# MOSFET.net
KiCad netlist of a schematic drawn in Altium Designer
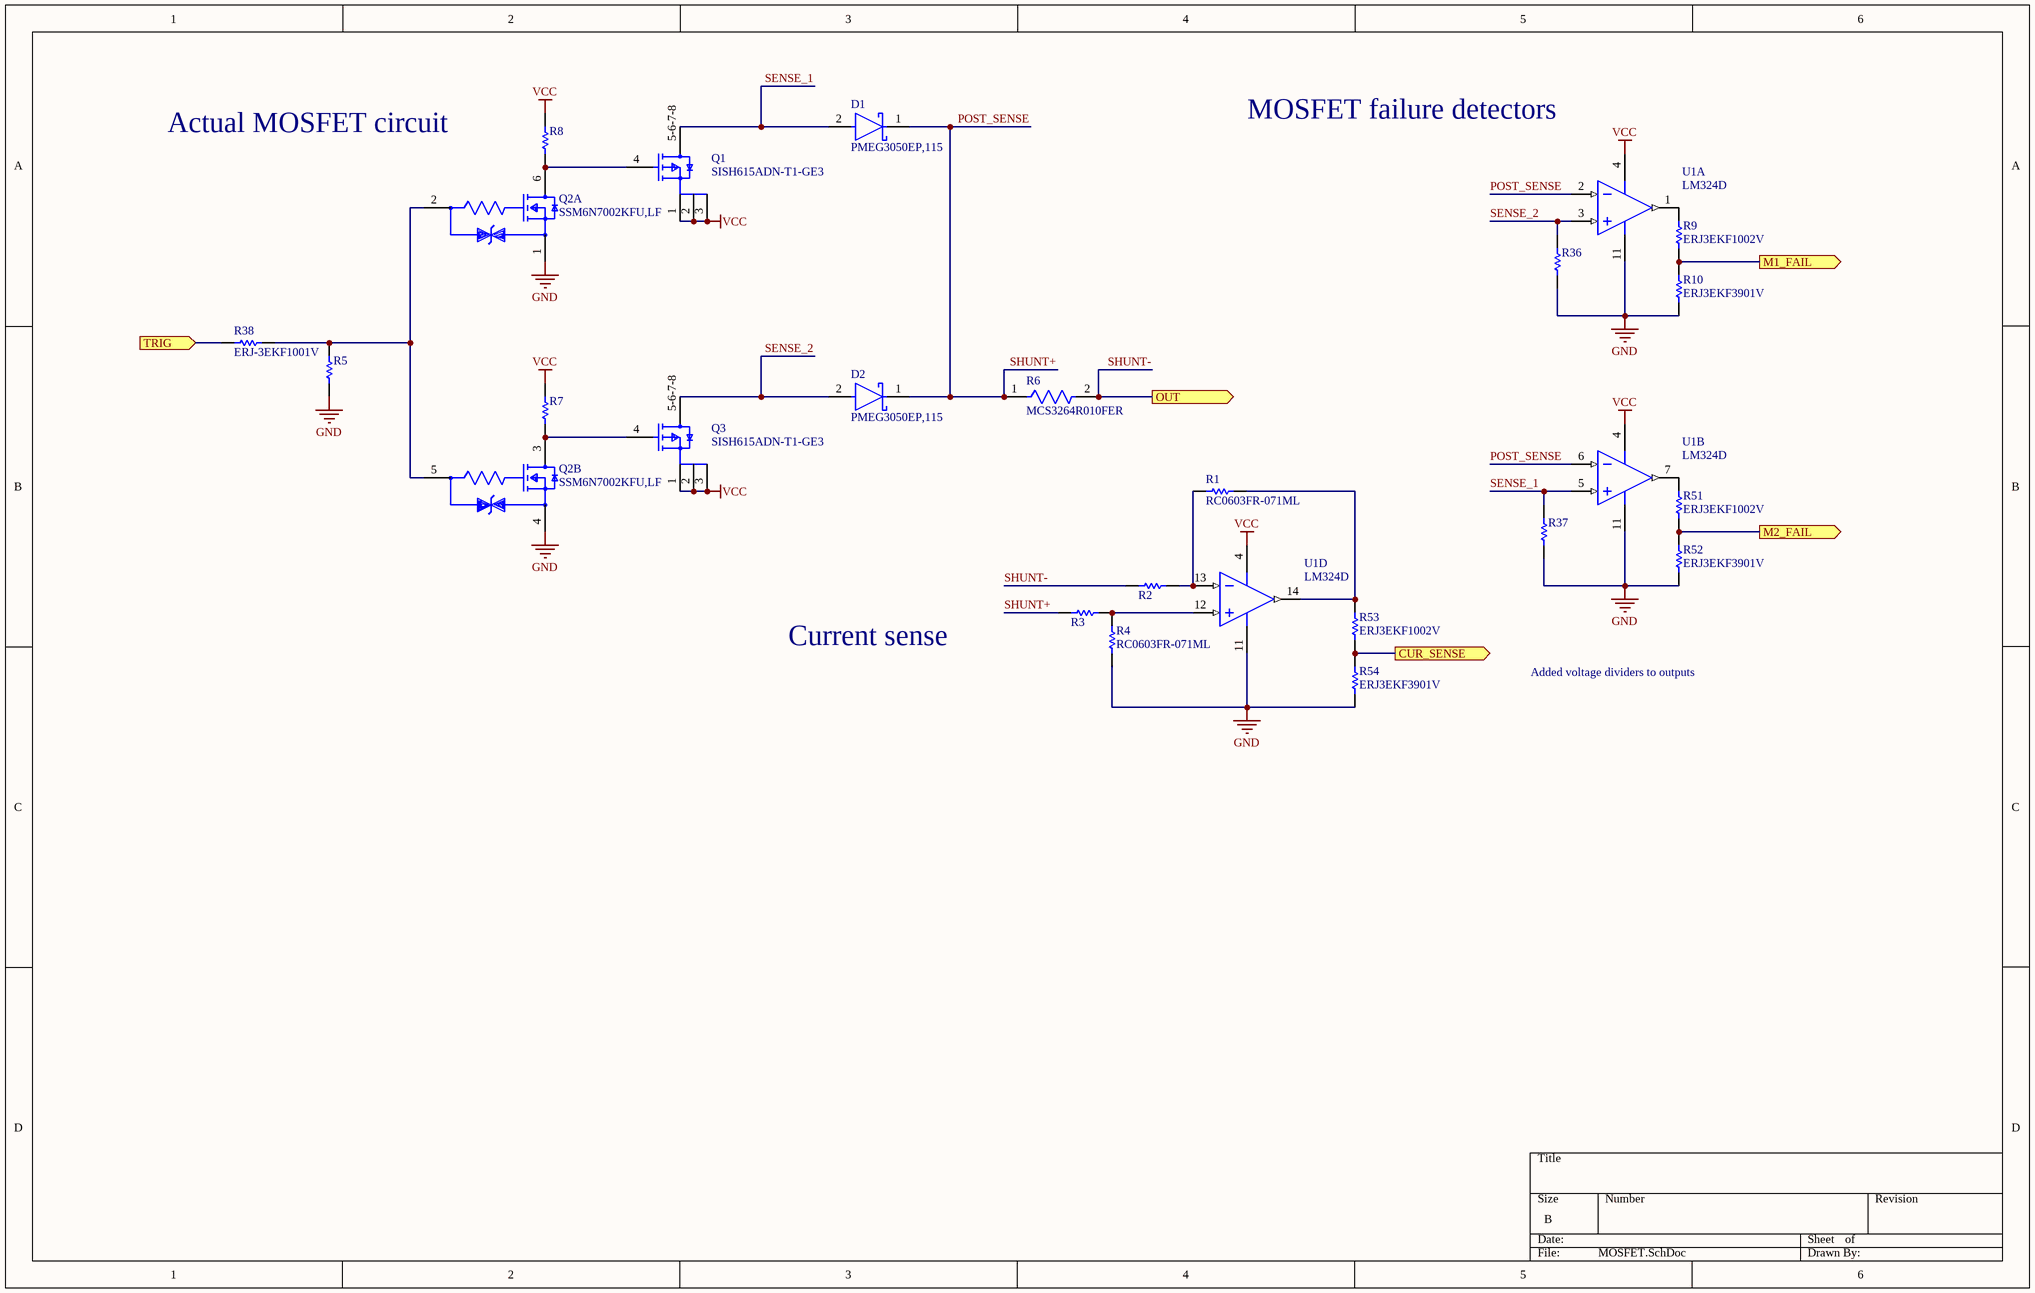
[diagram p0: MOSFET.SchDoc]

(export (version "E")
  (design (tool "Eeschema 10.0.6"))
  (components
    (comp (ref "D1")
      (value "PMEG3050EP,115")
      (footprint "FP-SOD128-MFG")
      (description "DIODE SCHOTTKY 30V 5A SOD128")
      (libsource (lib "Altium Content Vault") (part "1d6ec82d83fb6aee721767c19dac4b9"))
    )
    (comp (ref "D2")
      (value "PMEG3050EP,115")
      (footprint "FP-SOD128-MFG")
      (description "DIODE SCHOTTKY 30V 5A SOD128")
      (libsource (lib "Altium Content Vault") (part "1d6ec82d83fb6aee721767c19dac4b9"))
    )
    (comp (ref "Q1")
      (value "SISH615ADN-T1-GE3")
      (footprint "SISH615ADN-T1-GE3-Footprint-1")
      (description "Trans MOSFET P-CH 20V 22.1A 8-Pin PowerPAK 1212 EP T/R")
      (libsource (lib "uORocketry Hardware") (part "SISH615ADN-T1-GE3-Symbol-1"))
    )
    (comp (ref "Q2")
      (value "SSM6N7002KFU,LF")
      (footprint "FP-SSOP6-P-0_65A-MFG")
      (description "MOSFET 2N-CH 60V 0.3A")
      (libsource (lib "Altium Content Vault") (part "088aa6ac103fdeebe0d1c52ece6b7b9"))
    )
    (comp (ref "Q3")
      (value "SISH615ADN-T1-GE3")
      (footprint "SISH615ADN-T1-GE3-Footprint-1")
      (description "Trans MOSFET P-CH 20V 22.1A 8-Pin PowerPAK 1212 EP T/R")
      (libsource (lib "uORocketry Hardware") (part "SISH615ADN-T1-GE3-Symbol-1"))
    )
    (comp (ref "R1")
      (value "RC0603FR-071ML")
      (footprint "RESC1608X55X25LL10T15")
      (description "Chip Resistor, 1 MOhm, +/- 1%, 100 mW, -55 to 155 degC, 0603 (1608 Metric), RoHS, Tape and Reel")
      (fields (field (name "TOLERANCE") "20%"))
      (libsource (lib "Altium Content Vault") (part "RES-2"))
    )
    (comp (ref "R2")
      (value "ERJ3EKF1002V")
      (footprint "RESC1609X55X30LL15T15")
      (description "Chip Resistor, 10 KOhm, +/- 1%, 0.1 W, -55 to 155 degC, 0603 (1608 Metric), RoHS, Tape and Reel")
      (fields (field (name "TOLERANCE") "1%") (field (name "MANUFACTURER") "Panasonic"))
      (libsource (lib "Altium Content Vault") (part "RES-2"))
    )
    (comp (ref "R3")
      (value "ERJ3EKF1002V")
      (footprint "RESC1609X55X30LL15T15")
      (description "Chip Resistor, 10 KOhm, +/- 1%, 0.1 W, -55 to 155 degC, 0603 (1608 Metric), RoHS, Tape and Reel")
      (fields (field (name "TOLERANCE") "1%") (field (name "MANUFACTURER") "Panasonic"))
      (libsource (lib "Altium Content Vault") (part "RES-2"))
    )
    (comp (ref "R4")
      (value "RC0603FR-071ML")
      (footprint "RESC1608X55X25LL10T15")
      (description "Chip Resistor, 1 MOhm, +/- 1%, 100 mW, -55 to 155 degC, 0603 (1608 Metric), RoHS, Tape and Reel")
      (fields (field (name "TOLERANCE") "20%"))
      (libsource (lib "Altium Content Vault") (part "RES-2"))
    )
    (comp (ref "R5")
      (value "ERJ3EKF1002V")
      (footprint "RESC1609X55X30LL15T15")
      (description "Chip Resistor, 10 KOhm, +/- 1%, 0.1 W, -55 to 155 degC, 0603 (1608 Metric), RoHS, Tape and Reel")
      (fields (field (name "TOLERANCE") "1%") (field (name "MANUFACTURER") "Panasonic"))
      (libsource (lib "Altium Content Vault") (part "RES-2"))
    )
    (comp (ref "R6")
      (value "MCS3264R010FER")
      (footprint "FP-MCS3264-MFG")
      (description "RES SMD 10 MOHM 1% 2W 3264")
      (fields (field (name "TOLERANCE") "1%"))
      (libsource (lib "Altium Content Vault") (part "1029c3af85768c4190bb7ad29bc67b5"))
    )
    (comp (ref "R7")
      (value "ERJ3EKF1002V")
      (footprint "RESC1609X55X30LL15T15")
      (description "Chip Resistor, 10 KOhm, +/- 1%, 0.1 W, -55 to 155 degC, 0603 (1608 Metric), RoHS, Tape and Reel")
      (fields (field (name "TOLERANCE") "1%") (field (name "MANUFACTURER") "Panasonic"))
      (libsource (lib "Altium Content Vault") (part "RES-2"))
    )
    (comp (ref "R8")
      (value "ERJ3EKF1002V")
      (footprint "RESC1609X55X30LL15T15")
      (description "Chip Resistor, 10 KOhm, +/- 1%, 0.1 W, -55 to 155 degC, 0603 (1608 Metric), RoHS, Tape and Reel")
      (fields (field (name "TOLERANCE") "1%") (field (name "MANUFACTURER") "Panasonic"))
      (libsource (lib "Altium Content Vault") (part "RES-2"))
    )
    (comp (ref "R9")
      (value "ERJ3EKF1002V")
      (footprint "RESC1609X55X30LL15T15")
      (description "Chip Resistor, 10 KOhm, +/- 1%, 0.1 W, -55 to 155 degC, 0603 (1608 Metric), RoHS, Tape and Reel")
      (fields (field (name "TOLERANCE") "1%") (field (name "MANUFACTURER") "Panasonic"))
      (libsource (lib "Altium Content Vault") (part "RES-2"))
    )
    (comp (ref "R10")
      (value "ERJ3EKF3901V")
      (footprint "RESC1608X55X30ML15T15")
      (fields (field (name "MANUFACTURER") "Panasonic"))
      (libsource (lib "Altium Content Vault") (part "RES"))
    )
    (comp (ref "R36")
      (value "ERJ-3EKF1003V")
      (footprint "RESC1608X55X30ML15T15")
      (fields (field (name "MANUFACTURER") "Panasonic"))
      (libsource (lib "Altium Content Vault") (part "RES"))
    )
    (comp (ref "R37")
      (value "ERJ-3EKF1003V")
      (footprint "RESC1608X55X30ML15T15")
      (fields (field (name "MANUFACTURER") "Panasonic"))
      (libsource (lib "Altium Content Vault") (part "RES"))
    )
    (comp (ref "R38")
      (value "ERJ-3EKF1001V")
      (footprint "RESC1608X55X30LL15T15")
      (fields (field (name "MANUFACTURER") "Panasonic"))
      (libsource (lib "Altium Content Vault") (part "RES"))
    )
    (comp (ref "R51")
      (value "ERJ3EKF1002V")
      (footprint "RESC1609X55X30LL15T15")
      (description "Chip Resistor, 10 KOhm, +/- 1%, 0.1 W, -55 to 155 degC, 0603 (1608 Metric), RoHS, Tape and Reel")
      (fields (field (name "TOLERANCE") "1%") (field (name "MANUFACTURER") "Panasonic"))
      (libsource (lib "Altium Content Vault") (part "RES-2"))
    )
    (comp (ref "R52")
      (value "ERJ3EKF3901V")
      (footprint "RESC1608X55X30ML15T15")
      (fields (field (name "MANUFACTURER") "Panasonic"))
      (libsource (lib "Altium Content Vault") (part "RES"))
    )
    (comp (ref "R53")
      (value "ERJ3EKF1002V")
      (footprint "RESC1609X55X30LL15T15")
      (description "Chip Resistor, 10 KOhm, +/- 1%, 0.1 W, -55 to 155 degC, 0603 (1608 Metric), RoHS, Tape and Reel")
      (fields (field (name "TOLERANCE") "1%") (field (name "MANUFACTURER") "Panasonic"))
      (libsource (lib "Altium Content Vault") (part "RES-2"))
    )
    (comp (ref "R54")
      (value "ERJ3EKF3901V")
      (footprint "RESC1608X55X30ML15T15")
      (fields (field (name "MANUFACTURER") "Panasonic"))
      (libsource (lib "Altium Content Vault") (part "RES"))
    )
    (comp (ref "U1")
      (value "LM324D")
      (footprint "D0014A_L")
      (fields (field (name "MANUFACTURER") "Texas Instruments"))
      (libsource (lib "Altium Content Vault") (part "TI-LMX24_2902X-X14"))
    )
  )
  (nets
    (net (code "1") (name "/CUR_SENSE") (class "Default")
      (node (ref "R53") (pin "1") (pinfunction "1_1") (pintype "passive"))
      (node (ref "R54") (pin "2") (pinfunction "2_2") (pintype "passive"))
    )
    (net (code "2") (name "/M1_FAIL") (class "Default")
      (node (ref "R10") (pin "2") (pinfunction "2_2") (pintype "passive"))
      (node (ref "R9") (pin "1") (pinfunction "1_1") (pintype "passive"))
    )
    (net (code "3") (name "/M2_FAIL") (class "Default")
      (node (ref "R51") (pin "1") (pinfunction "1_1") (pintype "passive"))
      (node (ref "R52") (pin "2") (pinfunction "2_2") (pintype "passive"))
    )
    (net (code "4") (name "/POST_SENSE") (class "Default")
      (node (ref "D1") (pin "1") (pinfunction "C_1") (pintype "passive"))
      (node (ref "D2") (pin "1") (pinfunction "C_1") (pintype "passive"))
      (node (ref "R3") (pin "2") (pinfunction "2_2") (pintype "passive"))
      (node (ref "R6") (pin "1") (pinfunction "1_1") (pintype "passive"))
      (node (ref "U1") (pin "2") (pinfunction "1IN-_2") (pintype "input"))
      (node (ref "U1") (pin "6") (pinfunction "2IN-_6") (pintype "input"))
    )
    (net (code "5") (name "/SENSE_1") (class "Default")
      (node (ref "D1") (pin "2") (pinfunction "A_2") (pintype "passive"))
      (node (ref "Q1") (pin "5-6-7-8") (pinfunction "D_5-6-7-8") (pintype "passive"))
      (node (ref "R37") (pin "2") (pinfunction "2_2") (pintype "passive"))
      (node (ref "U1") (pin "5") (pinfunction "2IN+_5") (pintype "input"))
    )
    (net (code "6") (name "/SENSE_2") (class "Default")
      (node (ref "D2") (pin "2") (pinfunction "A_2") (pintype "passive"))
      (node (ref "Q3") (pin "5-6-7-8") (pinfunction "D_5-6-7-8") (pintype "passive"))
      (node (ref "R36") (pin "2") (pinfunction "2_2") (pintype "passive"))
      (node (ref "U1") (pin "3") (pinfunction "1IN+_3") (pintype "input"))
    )
    (net (code "7") (name "/SHUNT-") (class "Default")
      (node (ref "R2") (pin "2") (pinfunction "2_2") (pintype "passive"))
      (node (ref "R6") (pin "2") (pinfunction "2_2") (pintype "passive"))
    )
    (net (code "8") (name "/TRIG") (class "Default")
      (node (ref "R38") (pin "1") (pinfunction "1_1") (pintype "passive"))
    )
    (net (code "9") (name "GND") (class "Default")
      (node (ref "Q2") (pin "1") (pinfunction "Source1_1") (pintype "passive"))
      (node (ref "Q2") (pin "4") (pinfunction "Source2_4") (pintype "passive"))
      (node (ref "R10") (pin "1") (pinfunction "1_1") (pintype "passive"))
      (node (ref "R36") (pin "1") (pinfunction "1_1") (pintype "passive"))
      (node (ref "R37") (pin "1") (pinfunction "1_1") (pintype "passive"))
      (node (ref "R4") (pin "1") (pinfunction "1_1") (pintype "passive"))
      (node (ref "R5") (pin "1") (pinfunction "1_1") (pintype "passive"))
      (node (ref "R52") (pin "1") (pinfunction "1_1") (pintype "passive"))
      (node (ref "R54") (pin "1") (pinfunction "1_1") (pintype "passive"))
      (node (ref "U1") (pin "11") (pinfunction "GND_11") (pintype "power_in"))
    )
    (net (code "10") (name "Net-(Q1-G)") (class "Default")
      (node (ref "Q1") (pin "4") (pinfunction "G_4") (pintype "passive"))
      (node (ref "Q2") (pin "6") (pinfunction "Drain1_6") (pintype "passive"))
      (node (ref "R8") (pin "1") (pinfunction "1_1") (pintype "passive"))
    )
    (net (code "11") (name "Net-(Q2A-Gate1)") (class "Default")
      (node (ref "Q2") (pin "2") (pinfunction "Gate1_2") (pintype "passive"))
      (node (ref "Q2") (pin "5") (pinfunction "Gate2_5") (pintype "passive"))
      (node (ref "R38") (pin "2") (pinfunction "2_2") (pintype "passive"))
      (node (ref "R5") (pin "2") (pinfunction "2_2") (pintype "passive"))
    )
    (net (code "12") (name "Net-(Q2B-Drain2)") (class "Default")
      (node (ref "Q2") (pin "3") (pinfunction "Drain2_3") (pintype "passive"))
      (node (ref "Q3") (pin "4") (pinfunction "G_4") (pintype "passive"))
      (node (ref "R7") (pin "1") (pinfunction "1_1") (pintype "passive"))
    )
    (net (code "13") (name "Net-(U1A-1OUT)") (class "Default")
      (node (ref "R9") (pin "2") (pinfunction "2_2") (pintype "passive"))
      (node (ref "U1") (pin "1") (pinfunction "1OUT_1") (pintype "output"))
    )
    (net (code "14") (name "Net-(U1B-2OUT)") (class "Default")
      (node (ref "R51") (pin "2") (pinfunction "2_2") (pintype "passive"))
      (node (ref "U1") (pin "7") (pinfunction "2OUT_7") (pintype "output"))
    )
    (net (code "15") (name "Net-(U1D-4IN+)") (class "Default")
      (node (ref "R3") (pin "1") (pinfunction "1_1") (pintype "passive"))
      (node (ref "R4") (pin "2") (pinfunction "2_2") (pintype "passive"))
      (node (ref "U1") (pin "12") (pinfunction "4IN+_12") (pintype "input"))
    )
    (net (code "16") (name "Net-(U1D-4IN-)") (class "Default")
      (node (ref "R1") (pin "1") (pinfunction "1_1") (pintype "passive"))
      (node (ref "R2") (pin "1") (pinfunction "1_1") (pintype "passive"))
      (node (ref "U1") (pin "13") (pinfunction "4IN-_13") (pintype "input"))
    )
    (net (code "17") (name "Net-(U1D-4OUT)") (class "Default")
      (node (ref "R1") (pin "2") (pinfunction "2_2") (pintype "passive"))
      (node (ref "R53") (pin "2") (pinfunction "2_2") (pintype "passive"))
      (node (ref "U1") (pin "14") (pinfunction "4OUT_14") (pintype "output"))
    )
    (net (code "18") (name "VCC") (class "Default")
      (node (ref "Q1") (pin "1") (pinfunction "S_1") (pintype "passive"))
      (node (ref "Q1") (pin "2") (pinfunction "S_2") (pintype "passive"))
      (node (ref "Q1") (pin "3") (pinfunction "S_3") (pintype "passive"))
      (node (ref "Q3") (pin "1") (pinfunction "S_1") (pintype "passive"))
      (node (ref "Q3") (pin "2") (pinfunction "S_2") (pintype "passive"))
      (node (ref "Q3") (pin "3") (pinfunction "S_3") (pintype "passive"))
      (node (ref "R7") (pin "2") (pinfunction "2_2") (pintype "passive"))
      (node (ref "R8") (pin "2") (pinfunction "2_2") (pintype "passive"))
      (node (ref "U1") (pin "4") (pinfunction "VCC_4") (pintype "power_in"))
    )
  )
)
